# Sheet_1_2022-05-11.net
KiCad netlist of a schematic drawn in Altium Designer
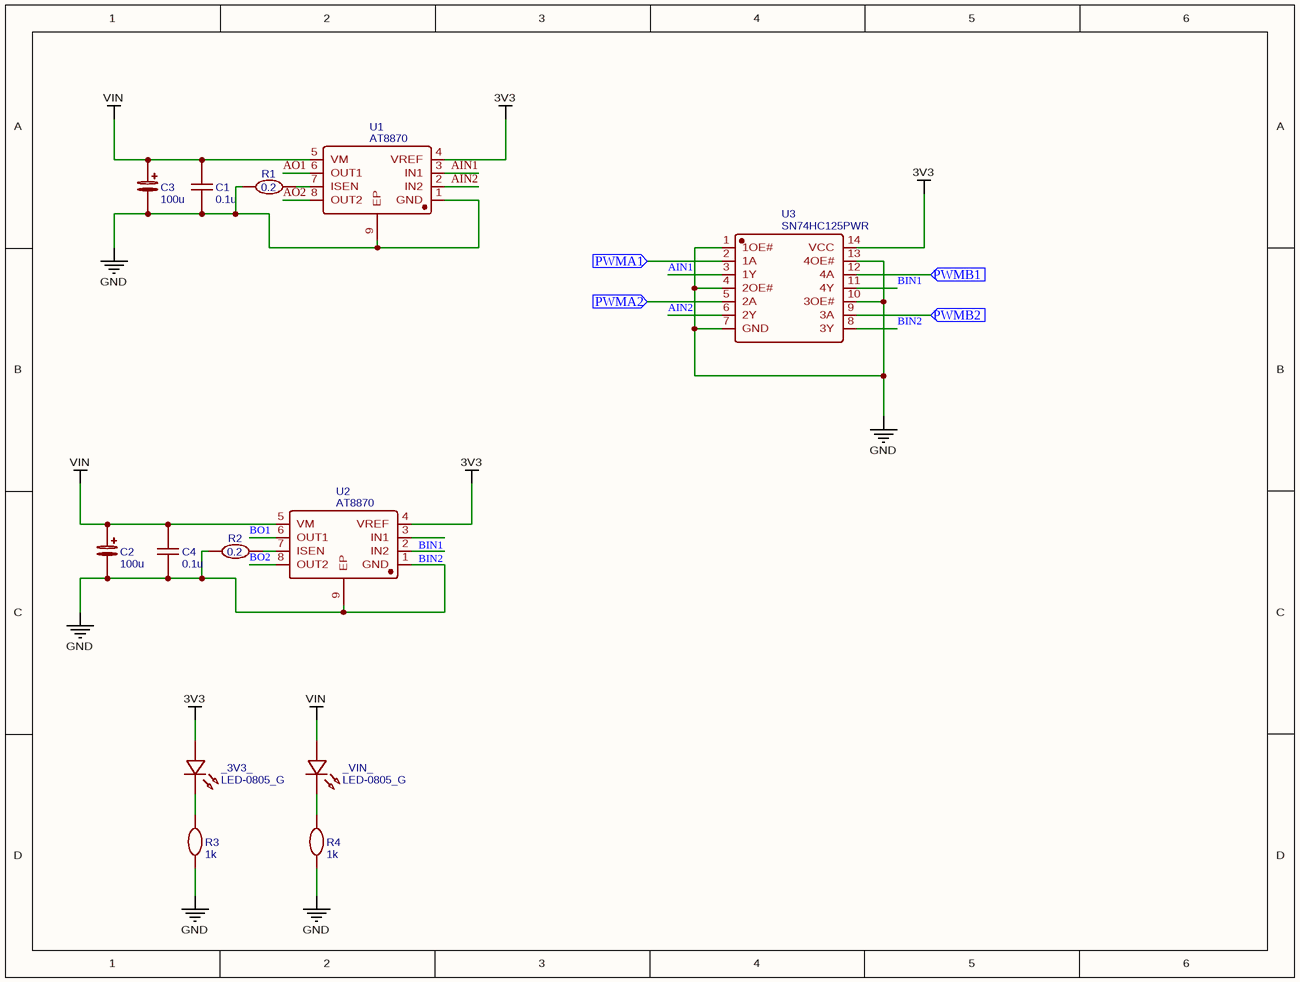
[diagram p0: Sheet_1_2022-05-11.schdoc]

(export (version "E")
  (design (tool "Eeschema 10.0.6"))
  (components
    (comp (ref "C1")
      (value "0.1u")
      (footprint "C0603")
      (fields (field (name "CONTRIBUTOR") "LCEDA_Lib"))
      (libsource (lib "altium-import") (part "root_1_0.1u_"))
    )
    (comp (ref "C2")
      (value "100u")
      (footprint "CAP-D6.3×H5.5")
      (fields (field (name "CONTRIBUTOR") "LCEDA_Lib"))
      (libsource (lib "altium-import") (part "root_3_100u_"))
    )
    (comp (ref "C3")
      (value "100u")
      (footprint "CAP-D6.3×H5.5")
      (fields (field (name "CONTRIBUTOR") "LCEDA_Lib"))
      (libsource (lib "altium-import") (part "root_3_100u_"))
    )
    (comp (ref "C4")
      (value "0.1u")
      (footprint "C0603")
      (fields (field (name "CONTRIBUTOR") "LCEDA_Lib"))
      (libsource (lib "altium-import") (part "root_1_0.1u_"))
    )
    (comp (ref "R1")
      (value "0.2")
      (footprint "R0603")
      (fields (field (name "CONTRIBUTOR") "LCEDA_Lib"))
      (libsource (lib "altium-import") (part "root_2_0.2_"))
    )
    (comp (ref "R2")
      (value "0.2")
      (footprint "R0603")
      (fields (field (name "CONTRIBUTOR") "LCEDA_Lib"))
      (libsource (lib "altium-import") (part "root_2_0.2_"))
    )
    (comp (ref "R3")
      (value "1k")
      (footprint "R0603")
      (fields (field (name "CONTRIBUTOR") "LCEDA_Lib"))
      (libsource (lib "altium-import") (part "root_1_1k_"))
    )
    (comp (ref "R4")
      (value "1k")
      (footprint "R0603")
      (fields (field (name "CONTRIBUTOR") "LCEDA_Lib"))
      (libsource (lib "altium-import") (part "root_1_1k_"))
    )
    (comp (ref "U1")
      (value "AT8870")
      (footprint "SOP-8_L4.9-W3.9-P1.27-LS6.0-BL-EP")
      (fields (field (name "BOM_SUPPLIER PART") "C191458") (field (name "CONTRIBUTOR") "LCSC"))
      (libsource (lib "altium-import") (part "root_2_AT8870_"))
    )
    (comp (ref "U2")
      (value "AT8870")
      (footprint "SOP-8_L4.9-W3.9-P1.27-LS6.0-BL-EP")
      (fields (field (name "BOM_SUPPLIER PART") "C191458") (field (name "CONTRIBUTOR") "LCSC"))
      (libsource (lib "altium-import") (part "root_2_AT8870_"))
    )
    (comp (ref "U3")
      (value "SN74HC125PWR")
      (footprint "TSSOP-14_L5.0-W4.4-P0.65-LS6.5-BL")
      (fields (field (name "BOM_SUPPLIER PART") "C132994") (field (name "CONTRIBUTOR") "LCSC"))
      (libsource (lib "altium-import") (part "root_0_SN74HC125PWR_"))
    )
    (comp (ref "_3V3_")
      (value "LED-0805_G")
      (footprint "LED0805_GREEN")
      (fields
        (field (name "BOM_MANUFACTURER PART") "NCD0805G1")
        (field (name "BOM_SUPPLIER PART") "C84260")
        (field (name "CONTRIBUTOR") "LCEDA_Lib")
      )
      (libsource (lib "altium-import") (part "root_3_LED-0805_G_"))
    )
    (comp (ref "_VIN_")
      (value "LED-0805_G")
      (footprint "LED0805_GREEN")
      (fields
        (field (name "BOM_MANUFACTURER PART") "NCD0805G1")
        (field (name "BOM_SUPPLIER PART") "C84260")
        (field (name "CONTRIBUTOR") "LCEDA_Lib")
      )
      (libsource (lib "altium-import") (part "root_3_LED-0805_G_"))
    )
  )
  (nets
    (net (code "1") (name "/AIN1") (class "Default")
      (node (ref "U1") (pin "3") (pinfunction "IN1_3") (pintype "passive"))
      (node (ref "U3") (pin "3") (pinfunction "1Y_3") (pintype "passive"))
    )
    (net (code "2") (name "/AIN2") (class "Default")
      (node (ref "U1") (pin "2") (pinfunction "IN2_2") (pintype "passive"))
      (node (ref "U3") (pin "6") (pinfunction "2Y_6") (pintype "passive"))
    )
    (net (code "3") (name "/AO1") (class "Default")
      (node (ref "U1") (pin "6") (pinfunction "OUT1_6") (pintype "passive"))
    )
    (net (code "4") (name "/AO2") (class "Default")
      (node (ref "U1") (pin "8") (pinfunction "OUT2_8") (pintype "passive"))
    )
    (net (code "5") (name "/BIN1") (class "Default")
      (node (ref "U2") (pin "3") (pinfunction "IN1_3") (pintype "passive"))
      (node (ref "U3") (pin "11") (pinfunction "4Y_11") (pintype "passive"))
    )
    (net (code "6") (name "/BIN2") (class "Default")
      (node (ref "U2") (pin "2") (pinfunction "IN2_2") (pintype "passive"))
      (node (ref "U3") (pin "8") (pinfunction "3Y_8") (pintype "passive"))
    )
    (net (code "7") (name "/BO1") (class "Default")
      (node (ref "U2") (pin "6") (pinfunction "OUT1_6") (pintype "passive"))
    )
    (net (code "8") (name "/BO2") (class "Default")
      (node (ref "U2") (pin "8") (pinfunction "OUT2_8") (pintype "passive"))
    )
    (net (code "9") (name "/PWMA1") (class "Default")
      (node (ref "U3") (pin "2") (pinfunction "1A_2") (pintype "passive"))
    )
    (net (code "10") (name "/PWMA2") (class "Default")
      (node (ref "U3") (pin "5") (pinfunction "2A_5") (pintype "passive"))
    )
    (net (code "11") (name "/PWMB1") (class "Default")
      (node (ref "U3") (pin "12") (pinfunction "4A_12") (pintype "passive"))
    )
    (net (code "12") (name "/PWMB2") (class "Default")
      (node (ref "U3") (pin "9") (pinfunction "3A_9") (pintype "passive"))
    )
    (net (code "13") (name "3V3") (class "Default")
      (node (ref "U1") (pin "4") (pinfunction "VREF_4") (pintype "passive"))
      (node (ref "U2") (pin "4") (pinfunction "VREF_4") (pintype "passive"))
      (node (ref "U3") (pin "14") (pinfunction "VCC_14") (pintype "passive"))
      (node (ref "_3V3_") (pin "1") (pinfunction "1_1") (pintype "passive"))
    )
    (net (code "14") (name "GND") (class "Default")
      (node (ref "C1") (pin "1") (pinfunction "1_1") (pintype "passive"))
      (node (ref "C2") (pin "2") (pinfunction "2_2") (pintype "passive"))
      (node (ref "C3") (pin "2") (pinfunction "2_2") (pintype "passive"))
      (node (ref "C4") (pin "1") (pinfunction "1_1") (pintype "passive"))
      (node (ref "R1") (pin "2") (pinfunction "2_2") (pintype "passive"))
      (node (ref "R2") (pin "2") (pinfunction "2_2") (pintype "passive"))
      (node (ref "R3") (pin "1") (pinfunction "1_1") (pintype "passive"))
      (node (ref "R4") (pin "1") (pinfunction "1_1") (pintype "passive"))
      (node (ref "U1") (pin "1") (pinfunction "GND_1") (pintype "passive"))
      (node (ref "U1") (pin "9") (pinfunction "EP_9") (pintype "passive"))
      (node (ref "U2") (pin "1") (pinfunction "GND_1") (pintype "passive"))
      (node (ref "U2") (pin "9") (pinfunction "EP_9") (pintype "passive"))
      (node (ref "U3") (pin "1") (pinfunction "1OE#_1") (pintype "passive"))
      (node (ref "U3") (pin "10") (pinfunction "3OE#_10") (pintype "passive"))
      (node (ref "U3") (pin "13") (pinfunction "4OE#_13") (pintype "passive"))
      (node (ref "U3") (pin "4") (pinfunction "2OE#_4") (pintype "passive"))
      (node (ref "U3") (pin "7") (pinfunction "GND_7") (pintype "passive"))
    )
    (net (code "15") (name "Net-(R3-Pad2)") (class "Default")
      (node (ref "R3") (pin "2") (pinfunction "2_2") (pintype "passive"))
      (node (ref "_3V3_") (pin "2") (pinfunction "2_2") (pintype "passive"))
    )
    (net (code "16") (name "Net-(R4-Pad2)") (class "Default")
      (node (ref "R4") (pin "2") (pinfunction "2_2") (pintype "passive"))
      (node (ref "_VIN_") (pin "2") (pinfunction "2_2") (pintype "passive"))
    )
    (net (code "17") (name "Net-(U1-ISEN)") (class "Default")
      (node (ref "R1") (pin "1") (pinfunction "1_1") (pintype "passive"))
      (node (ref "U1") (pin "7") (pinfunction "ISEN_7") (pintype "passive"))
    )
    (net (code "18") (name "Net-(U2-ISEN)") (class "Default")
      (node (ref "R2") (pin "1") (pinfunction "1_1") (pintype "passive"))
      (node (ref "U2") (pin "7") (pinfunction "ISEN_7") (pintype "passive"))
    )
    (net (code "19") (name "VIN") (class "Default")
      (node (ref "C1") (pin "2") (pinfunction "2_2") (pintype "passive"))
      (node (ref "C2") (pin "1") (pinfunction "1_1") (pintype "passive"))
      (node (ref "C3") (pin "1") (pinfunction "1_1") (pintype "passive"))
      (node (ref "C4") (pin "2") (pinfunction "2_2") (pintype "passive"))
      (node (ref "U1") (pin "5") (pinfunction "VM_5") (pintype "passive"))
      (node (ref "U2") (pin "5") (pinfunction "VM_5") (pintype "passive"))
      (node (ref "_VIN_") (pin "1") (pinfunction "1_1") (pintype "passive"))
    )
  )
)
